# main_16_writer.net
KiCad netlist of a schematic drawn in EAGLE
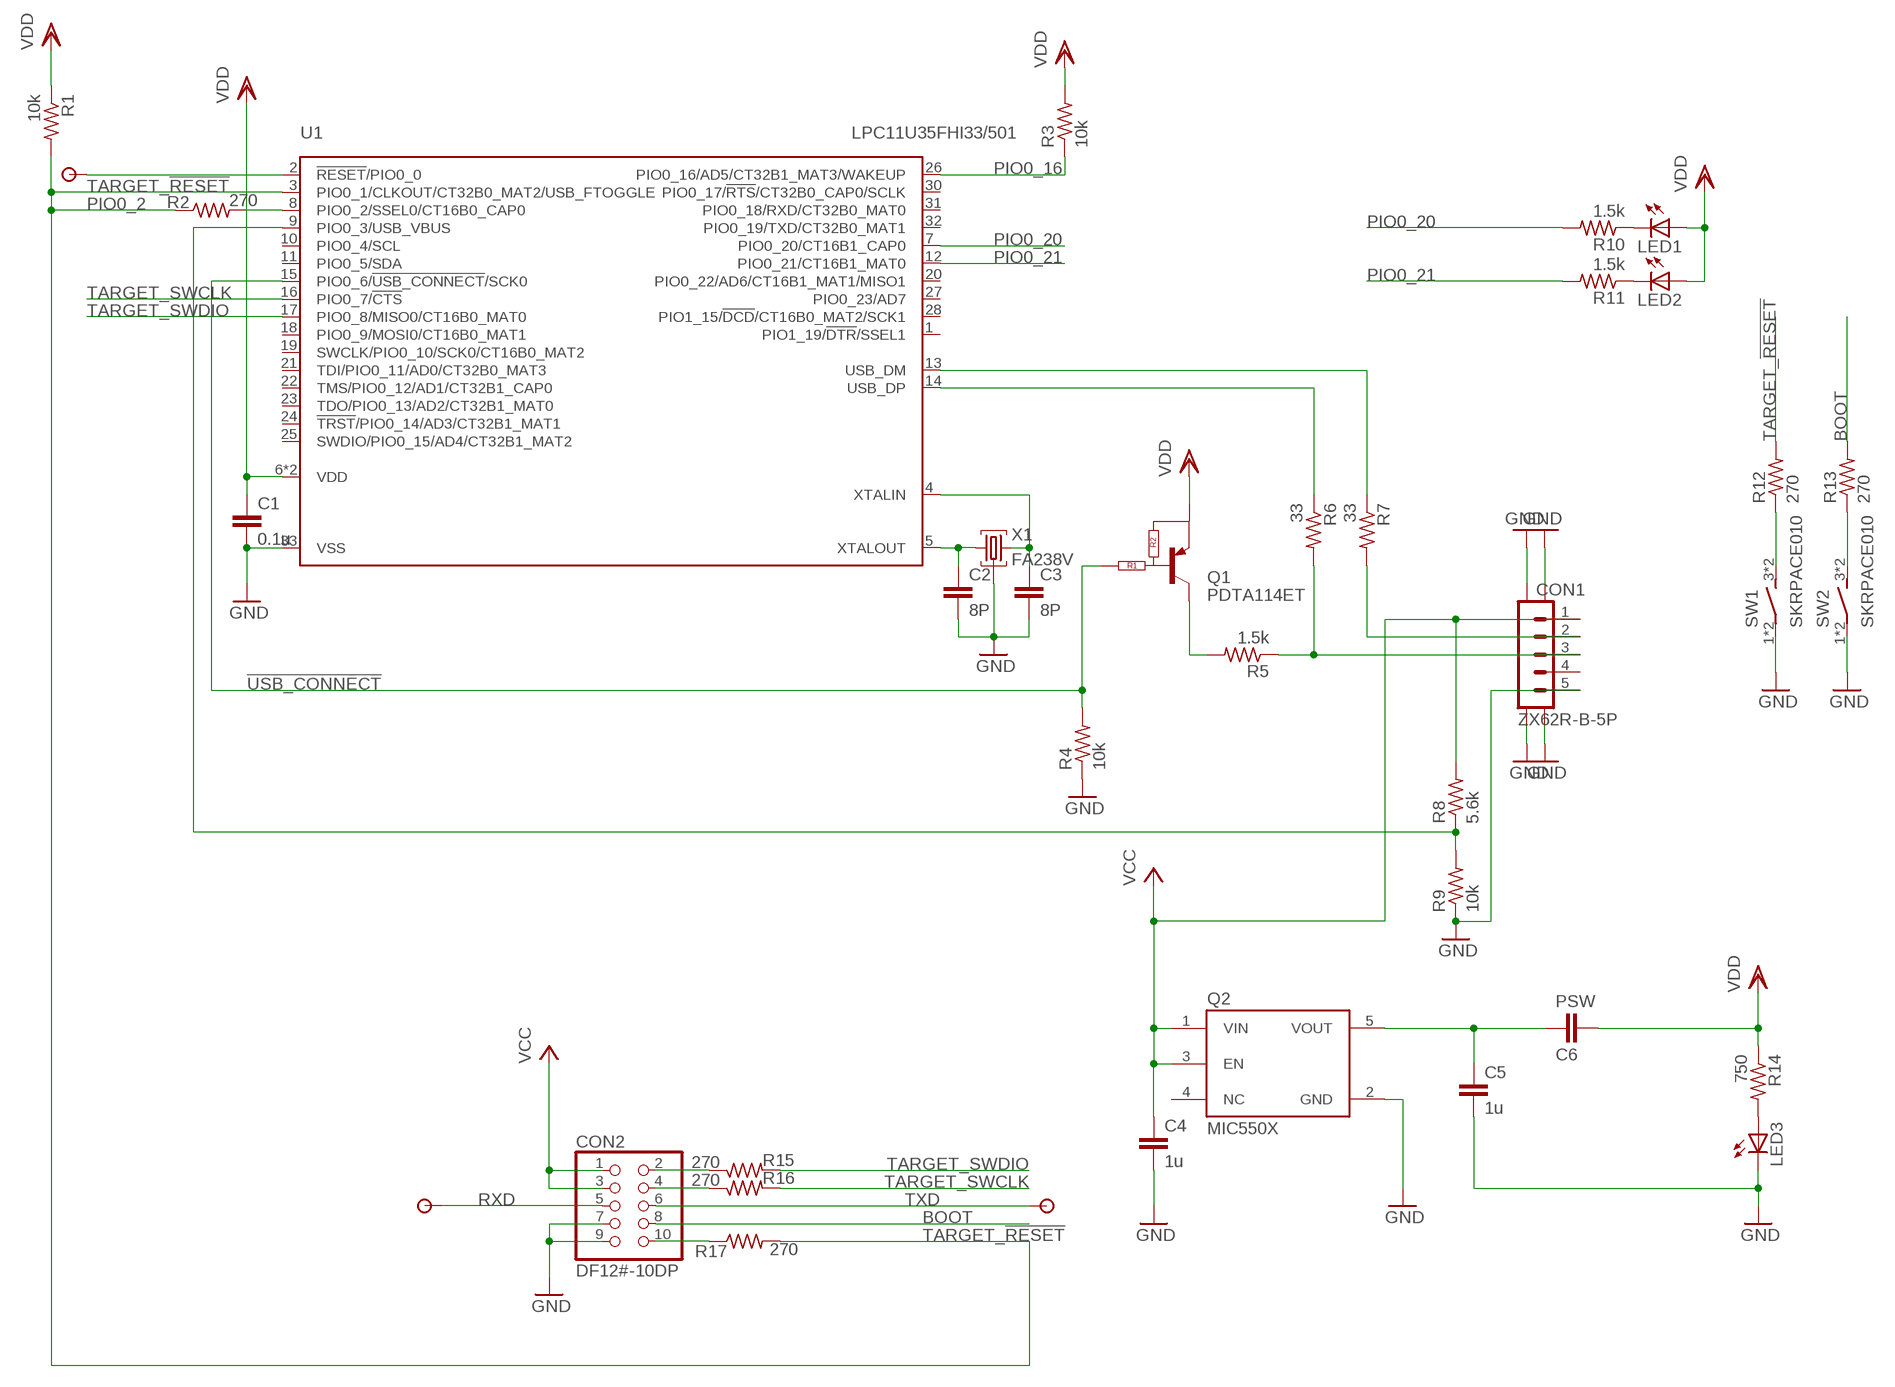
[diagram p0: schematic, sheet 1]

(export (version "E")
  (design (tool "Eeschema 10.0.6"))
  (components
    (comp (ref "C1")
      (value "0.1u")
      (footprint "eagle-import:C0402")
      (libsource (lib "eagle-import") (part "C-EUC0402"))
    )
    (comp (ref "C2")
      (value "8P")
      (footprint "eagle-import:C0402")
      (libsource (lib "eagle-import") (part "C-EUC0402"))
    )
    (comp (ref "C3")
      (value "8P")
      (footprint "eagle-import:C0402")
      (libsource (lib "eagle-import") (part "C-EUC0402"))
    )
    (comp (ref "C4")
      (value "1u")
      (footprint "eagle-import:C0402")
      (libsource (lib "eagle-import") (part "C-EUC0402"))
    )
    (comp (ref "C5")
      (value "1u")
      (footprint "eagle-import:C0402")
      (libsource (lib "eagle-import") (part "C-EUC0402"))
    )
    (comp (ref "C6")
      (value "PSW")
      (footprint "eagle-import:C3225")
      (libsource (lib "eagle-import") (part "C-EUC3225"))
    )
    (comp (ref "CON1")
      (value "ZX62R-B-5P")
      (footprint "eagle-import:MICRO-B")
      (libsource (lib "eagle-import") (part "ZX62R-B-5P"))
    )
    (comp (ref "CON2")
      (value "DF12#-10DP")
      (footprint "eagle-import:DF12D-10DP")
      (libsource (lib "eagle-import") (part "DF12#-10DP"))
    )
    (comp (ref "LED1")
      (value "LEDSML0603")
      (footprint "eagle-import:SML0603")
      (libsource (lib "eagle-import") (part "LEDSML0603"))
    )
    (comp (ref "LED2")
      (value "LEDSML0603")
      (footprint "eagle-import:SML0603")
      (libsource (lib "eagle-import") (part "LEDSML0603"))
    )
    (comp (ref "LED3")
      (value "LEDSML0603")
      (footprint "eagle-import:SML0603")
      (libsource (lib "eagle-import") (part "LEDSML0603"))
    )
    (comp (ref "Q1")
      (value "PDTA114ET")
      (footprint "eagle-import:SOT23")
      (libsource (lib "eagle-import") (part "PDTA114TE"))
    )
    (comp (ref "Q2")
      (value "MIC550X")
      (footprint "eagle-import:SOT23_5PIN")
      (libsource (lib "eagle-import") (part "MIC550X"))
    )
    (comp (ref "R1")
      (value "10k")
      (footprint "eagle-import:R0402")
      (libsource (lib "eagle-import") (part "R-US_R0402"))
    )
    (comp (ref "R2")
      (value "270")
      (footprint "eagle-import:R0402")
      (libsource (lib "eagle-import") (part "R-US_R0402"))
    )
    (comp (ref "R3")
      (value "10k")
      (footprint "eagle-import:R0402")
      (libsource (lib "eagle-import") (part "R-US_R0402"))
    )
    (comp (ref "R4")
      (value "10k")
      (footprint "eagle-import:R0402")
      (libsource (lib "eagle-import") (part "R-US_R0402"))
    )
    (comp (ref "R5")
      (value "1.5k")
      (footprint "eagle-import:R0402")
      (libsource (lib "eagle-import") (part "R-US_R0402"))
    )
    (comp (ref "R6")
      (value "33")
      (footprint "eagle-import:R0402")
      (libsource (lib "eagle-import") (part "R-US_R0402"))
    )
    (comp (ref "R7")
      (value "33")
      (footprint "eagle-import:R0402")
      (libsource (lib "eagle-import") (part "R-US_R0402"))
    )
    (comp (ref "R8")
      (value "5.6k")
      (footprint "eagle-import:R0402")
      (libsource (lib "eagle-import") (part "R-US_R0402"))
    )
    (comp (ref "R9")
      (value "10k")
      (footprint "eagle-import:R0402")
      (libsource (lib "eagle-import") (part "R-US_R0402"))
    )
    (comp (ref "R10")
      (value "1.5k")
      (footprint "eagle-import:R0402")
      (libsource (lib "eagle-import") (part "R-US_R0402"))
    )
    (comp (ref "R11")
      (value "1.5k")
      (footprint "eagle-import:R0402")
      (libsource (lib "eagle-import") (part "R-US_R0402"))
    )
    (comp (ref "R12")
      (value "270")
      (footprint "eagle-import:R0402")
      (libsource (lib "eagle-import") (part "R-US_R0402"))
    )
    (comp (ref "R13")
      (value "270")
      (footprint "eagle-import:R0402")
      (libsource (lib "eagle-import") (part "R-US_R0402"))
    )
    (comp (ref "R14")
      (value "750")
      (footprint "eagle-import:R0402")
      (libsource (lib "eagle-import") (part "R-US_R0402"))
    )
    (comp (ref "R15")
      (value "270")
      (footprint "eagle-import:R0402")
      (libsource (lib "eagle-import") (part "R-US_R0402"))
    )
    (comp (ref "R16")
      (value "270")
      (footprint "eagle-import:R0402")
      (libsource (lib "eagle-import") (part "R-US_R0402"))
    )
    (comp (ref "R17")
      (value "270")
      (footprint "eagle-import:R0402")
      (libsource (lib "eagle-import") (part "R-US_R0402"))
    )
    (comp (ref "SW1")
      (value "SKRPACE010")
      (footprint "eagle-import:SKRPACE010")
      (libsource (lib "eagle-import") (part "SKRPACE010"))
    )
    (comp (ref "SW2")
      (value "SKRPACE010")
      (footprint "eagle-import:SKRPACE010")
      (libsource (lib "eagle-import") (part "SKRPACE010"))
    )
    (comp (ref "U$1")
      (value "TESTPAD")
      (footprint "eagle-import:TESTPAD")
      (libsource (lib "eagle-import") (part "TESTPAD"))
    )
    (comp (ref "U$2")
      (value "TESTPAD")
      (footprint "eagle-import:TESTPAD")
      (libsource (lib "eagle-import") (part "TESTPAD"))
    )
    (comp (ref "U$3")
      (value "TESTPAD")
      (footprint "eagle-import:TESTPAD")
      (libsource (lib "eagle-import") (part "TESTPAD"))
    )
    (comp (ref "U1")
      (value "LPC11U35FHI33/501")
      (footprint "eagle-import:SOT617-3")
      (libsource (lib "eagle-import") (part "LPC11U35FHI33/501"))
    )
    (comp (ref "X1")
      (value "FA238V")
      (footprint "eagle-import:V66RA")
      (libsource (lib "eagle-import") (part "FA238V"))
    )
  )
  (nets
    (net (code "1") (name "/BOOT") (class "Default")
      (node (ref "CON2") (pin "8") (pinfunction "8_8") (pintype "passive"))
      (node (ref "R13") (pin "2") (pinfunction "2_2") (pintype "passive"))
    )
    (net (code "2") (name "/PIO0_2") (class "Default")
      (node (ref "R2") (pin "2") (pinfunction "2_2") (pintype "passive"))
      (node (ref "U1") (pin "8") (pinfunction "PIO0_2/SSEL0/CT16B0_CAP0_8") (pintype "bidirectional"))
    )
    (net (code "3") (name "/PIO0_16") (class "Default")
      (node (ref "R3") (pin "1") (pinfunction "1_1") (pintype "passive"))
      (node (ref "U1") (pin "26") (pinfunction "PIO0_16/AD5/CT32B1_MAT3/WAKEUP_26") (pintype "bidirectional"))
    )
    (net (code "4") (name "/PIO0_20") (class "Default")
      (node (ref "R10") (pin "2") (pinfunction "2_2") (pintype "passive"))
      (node (ref "U1") (pin "7") (pinfunction "PIO0_20/CT16B1_CAP0_7") (pintype "bidirectional"))
    )
    (net (code "5") (name "/PIO0_21") (class "Default")
      (node (ref "R11") (pin "2") (pinfunction "2_2") (pintype "passive"))
      (node (ref "U1") (pin "12") (pinfunction "PIO0_21/CT16B1_MAT0_12") (pintype "bidirectional"))
    )
    (net (code "6") (name "/RXD") (class "Default")
      (node (ref "CON2") (pin "5") (pinfunction "5_5") (pintype "passive"))
      (node (ref "U$2") (pin "P$1") (pinfunction "P$1_P$1") (pintype "passive"))
    )
    (net (code "7") (name "/TARGET_SWCLK") (class "Default")
      (node (ref "R16") (pin "2") (pinfunction "2_2") (pintype "passive"))
      (node (ref "U1") (pin "16") (pinfunction "PIO0_7/~{CTS}_16") (pintype "bidirectional"))
    )
    (net (code "8") (name "/TARGET_SWDIO") (class "Default")
      (node (ref "R15") (pin "2") (pinfunction "2_2") (pintype "passive"))
      (node (ref "U1") (pin "17") (pinfunction "PIO0_8/MISO0/CT16B0_MAT0_17") (pintype "bidirectional"))
    )
    (net (code "9") (name "/TARGET_~{RESET}") (class "Default")
      (node (ref "R1") (pin "2") (pinfunction "2_2") (pintype "passive"))
      (node (ref "R12") (pin "2") (pinfunction "2_2") (pintype "passive"))
      (node (ref "R17") (pin "2") (pinfunction "2_2") (pintype "passive"))
      (node (ref "R2") (pin "1") (pinfunction "1_1") (pintype "passive"))
      (node (ref "U1") (pin "3") (pinfunction "PIO0_1/CLKOUT/CT32B0_MAT2/USB_FTOGGLE_3") (pintype "bidirectional"))
    )
    (net (code "10") (name "/TXD") (class "Default")
      (node (ref "CON2") (pin "6") (pinfunction "6_6") (pintype "passive"))
      (node (ref "U$1") (pin "P$1") (pinfunction "P$1_P$1") (pintype "passive"))
    )
    (net (code "11") (name "/~{USB_CONNECT}") (class "Default")
      (node (ref "Q1") (pin "1") (pinfunction "INPUT_1") (pintype "passive"))
      (node (ref "R4") (pin "2") (pinfunction "2_2") (pintype "passive"))
      (node (ref "U1") (pin "15") (pinfunction "PIO0_6/~{USB_CONNECT}/SCK0_15") (pintype "bidirectional"))
    )
    (net (code "12") (name "GND") (class "Default")
      (node (ref "C1") (pin "2") (pinfunction "2_2") (pintype "passive"))
      (node (ref "C2") (pin "2") (pinfunction "2_2") (pintype "passive"))
      (node (ref "C3") (pin "2") (pinfunction "2_2") (pintype "passive"))
      (node (ref "C4") (pin "2") (pinfunction "2_2") (pintype "passive"))
      (node (ref "C5") (pin "2") (pinfunction "2_2") (pintype "passive"))
      (node (ref "CON1") (pin "5") (pinfunction "1.VBUS_5") (pintype "passive"))
      (node (ref "CON1") (pin "CASE@1") (pinfunction "1_CASE@1") (pintype "bidirectional"))
      (node (ref "CON1") (pin "CASE@2") (pinfunction "2_CASE@2") (pintype "bidirectional"))
      (node (ref "CON1") (pin "CASE@3") (pinfunction "3_CASE@3") (pintype "bidirectional"))
      (node (ref "CON1") (pin "CASE@4") (pinfunction "4_CASE@4") (pintype "bidirectional"))
      (node (ref "CON2") (pin "7") (pinfunction "7_7") (pintype "passive"))
      (node (ref "CON2") (pin "9") (pinfunction "9_9") (pintype "passive"))
      (node (ref "LED3") (pin "C") (pinfunction "C_C") (pintype "passive"))
      (node (ref "Q2") (pin "2") (pinfunction "GND_2") (pintype "power_in"))
      (node (ref "R4") (pin "1") (pinfunction "1_1") (pintype "passive"))
      (node (ref "R9") (pin "1") (pinfunction "1_1") (pintype "passive"))
      (node (ref "SW1") (pin "1") (pinfunction "P_1") (pintype "passive"))
      (node (ref "SW1") (pin "2") (pinfunction "P_2") (pintype "passive"))
      (node (ref "SW2") (pin "1") (pinfunction "P_1") (pintype "passive"))
      (node (ref "SW2") (pin "2") (pinfunction "P_2") (pintype "passive"))
      (node (ref "U1") (pin "33") (pinfunction "VSS_33") (pintype "power_in"))
      (node (ref "X1") (pin "P2GND") (pinfunction "GND_P2GND") (pintype "bidirectional"))
      (node (ref "X1") (pin "P4GND") (pinfunction "GND_P4GND") (pintype "bidirectional"))
    )
    (net (code "13") (name "Net-(CON1-3.D+)") (class "Default")
      (node (ref "CON1") (pin "3") (pinfunction "3.D+_3") (pintype "passive"))
      (node (ref "R5") (pin "1") (pinfunction "1_1") (pintype "passive"))
      (node (ref "R6") (pin "2") (pinfunction "2_2") (pintype "passive"))
    )
    (net (code "14") (name "Net-(CON1-4.ID)") (class "Default")
      (node (ref "CON1") (pin "2") (pinfunction "4.ID_2") (pintype "passive"))
      (node (ref "R7") (pin "2") (pinfunction "2_2") (pintype "passive"))
    )
    (net (code "15") (name "Net-(CON2-Pad2)") (class "Default")
      (node (ref "CON2") (pin "2") (pinfunction "2_2") (pintype "passive"))
      (node (ref "R15") (pin "1") (pinfunction "1_1") (pintype "passive"))
    )
    (net (code "16") (name "Net-(CON2-Pad4)") (class "Default")
      (node (ref "CON2") (pin "4") (pinfunction "4_4") (pintype "passive"))
      (node (ref "R16") (pin "1") (pinfunction "1_1") (pintype "passive"))
    )
    (net (code "17") (name "Net-(CON2-Pad10)") (class "Default")
      (node (ref "CON2") (pin "10") (pinfunction "10_10") (pintype "passive"))
      (node (ref "R17") (pin "1") (pinfunction "1_1") (pintype "passive"))
    )
    (net (code "18") (name "Net-(LED1-PadC)") (class "Default")
      (node (ref "LED1") (pin "C") (pinfunction "C_C") (pintype "passive"))
      (node (ref "R10") (pin "1") (pinfunction "1_1") (pintype "passive"))
    )
    (net (code "19") (name "Net-(LED2-PadC)") (class "Default")
      (node (ref "LED2") (pin "C") (pinfunction "C_C") (pintype "passive"))
      (node (ref "R11") (pin "1") (pinfunction "1_1") (pintype "passive"))
    )
    (net (code "20") (name "Net-(LED3-PadA)") (class "Default")
      (node (ref "LED3") (pin "A") (pinfunction "A_A") (pintype "passive"))
      (node (ref "R14") (pin "2") (pinfunction "2_2") (pintype "passive"))
    )
    (net (code "21") (name "Net-(Q1-C)") (class "Default")
      (node (ref "Q1") (pin "3") (pinfunction "C_3") (pintype "passive"))
      (node (ref "R5") (pin "2") (pinfunction "2_2") (pintype "passive"))
    )
    (net (code "22") (name "Net-(Q2-VOUT)") (class "Default")
      (node (ref "C5") (pin "1") (pinfunction "1_1") (pintype "passive"))
      (node (ref "C6") (pin "2") (pinfunction "2_2") (pintype "passive"))
      (node (ref "Q2") (pin "5") (pinfunction "VOUT_5") (pintype "output"))
    )
    (net (code "23") (name "Net-(R12-Pad1)") (class "Default")
      (node (ref "R12") (pin "1") (pinfunction "1_1") (pintype "passive"))
      (node (ref "SW1") (pin "3") (pinfunction "S_3") (pintype "passive"))
      (node (ref "SW1") (pin "4") (pinfunction "S_4") (pintype "passive"))
    )
    (net (code "24") (name "Net-(R13-Pad1)") (class "Default")
      (node (ref "R13") (pin "1") (pinfunction "1_1") (pintype "passive"))
      (node (ref "SW2") (pin "3") (pinfunction "S_3") (pintype "passive"))
      (node (ref "SW2") (pin "4") (pinfunction "S_4") (pintype "passive"))
    )
    (net (code "25") (name "Net-(U1-PIO0_3{slash}USB_VBUS)") (class "Default")
      (node (ref "R8") (pin "1") (pinfunction "1_1") (pintype "passive"))
      (node (ref "R9") (pin "2") (pinfunction "2_2") (pintype "passive"))
      (node (ref "U1") (pin "9") (pinfunction "PIO0_3/USB_VBUS_9") (pintype "bidirectional"))
    )
    (net (code "26") (name "Net-(U1-USB_DM)") (class "Default")
      (node (ref "R7") (pin "1") (pinfunction "1_1") (pintype "passive"))
      (node (ref "U1") (pin "13") (pinfunction "USB_DM_13") (pintype "bidirectional"))
    )
    (net (code "27") (name "Net-(U1-USB_DP)") (class "Default")
      (node (ref "R6") (pin "1") (pinfunction "1_1") (pintype "passive"))
      (node (ref "U1") (pin "14") (pinfunction "USB_DP_14") (pintype "bidirectional"))
    )
    (net (code "28") (name "Net-(U1-XTALIN)") (class "Default")
      (node (ref "C3") (pin "1") (pinfunction "1_1") (pintype "passive"))
      (node (ref "U1") (pin "4") (pinfunction "XTALIN_4") (pintype "input"))
      (node (ref "X1") (pin "P3X2") (pinfunction "X2_P3X2") (pintype "output"))
    )
    (net (code "29") (name "Net-(U1-XTALOUT)") (class "Default")
      (node (ref "C2") (pin "1") (pinfunction "1_1") (pintype "passive"))
      (node (ref "U1") (pin "5") (pinfunction "XTALOUT_5") (pintype "output"))
      (node (ref "X1") (pin "P1X1") (pinfunction "X1_P1X1") (pintype "output"))
    )
    (net (code "30") (name "Net-(U1-~{RESET}{slash}PIO0_0)") (class "Default")
      (node (ref "U$3") (pin "P$1") (pinfunction "P$1_P$1") (pintype "passive"))
      (node (ref "U1") (pin "2") (pinfunction "~{RESET}/PIO0_0_2") (pintype "bidirectional"))
    )
    (net (code "31") (name "VCC") (class "Default")
      (node (ref "C4") (pin "1") (pinfunction "1_1") (pintype "passive"))
      (node (ref "CON1") (pin "1") (pinfunction "5.GND_1") (pintype "passive"))
      (node (ref "CON2") (pin "1") (pinfunction "1_1") (pintype "passive"))
      (node (ref "CON2") (pin "3") (pinfunction "3_3") (pintype "passive"))
      (node (ref "Q2") (pin "1") (pinfunction "VIN_1") (pintype "input"))
      (node (ref "Q2") (pin "3") (pinfunction "EN_3") (pintype "input"))
      (node (ref "R8") (pin "2") (pinfunction "2_2") (pintype "passive"))
    )
    (net (code "32") (name "VDD") (class "Default")
      (node (ref "C1") (pin "1") (pinfunction "1_1") (pintype "passive"))
      (node (ref "C6") (pin "1") (pinfunction "1_1") (pintype "passive"))
      (node (ref "LED1") (pin "A") (pinfunction "A_A") (pintype "passive"))
      (node (ref "LED2") (pin "A") (pinfunction "A_A") (pintype "passive"))
      (node (ref "Q1") (pin "2") (pinfunction "E_2") (pintype "passive"))
      (node (ref "R1") (pin "1") (pinfunction "1_1") (pintype "passive"))
      (node (ref "R14") (pin "1") (pinfunction "1_1") (pintype "passive"))
      (node (ref "R3") (pin "2") (pinfunction "2_2") (pintype "passive"))
      (node (ref "U1") (pin "29") (pinfunction "VDD_29") (pintype "power_in"))
      (node (ref "U1") (pin "6") (pinfunction "VDD_6") (pintype "power_in"))
    )
    (net (code "33") (name "unconnected-(CON1-2.D--Pad4)") (class "Default")
      (node (ref "CON1") (pin "4") (pinfunction "2.D-_4") (pintype "passive"))
    )
    (net (code "34") (name "unconnected-(Q2-NC-Pad4)") (class "Default")
      (node (ref "Q2") (pin "4") (pinfunction "NC_4") (pintype "no_connect"))
    )
    (net (code "35") (name "unconnected-(U1-PIO0_4{slash}SCL-Pad10)") (class "Default")
      (node (ref "U1") (pin "10") (pinfunction "PIO0_4/SCL_10") (pintype "bidirectional"))
    )
    (net (code "36") (name "unconnected-(U1-PIO0_5{slash}SDA-Pad11)") (class "Default")
      (node (ref "U1") (pin "11") (pinfunction "PIO0_5/SDA_11") (pintype "bidirectional"))
    )
    (net (code "37") (name "unconnected-(U1-PIO0_9{slash}MOSI0{slash}CT16B0_MAT1-Pad18)") (class "Default")
      (node (ref "U1") (pin "18") (pinfunction "PIO0_9/MOSI0/CT16B0_MAT1_18") (pintype "bidirectional"))
    )
    (net (code "38") (name "unconnected-(U1-PIO0_17{slash}~{RTS}{slash}CT32B0_CAP0{slash}SCLK-Pad30)") (class "Default")
      (node (ref "U1") (pin "30") (pinfunction "PIO0_17/~{RTS}/CT32B0_CAP0/SCLK_30") (pintype "bidirectional"))
    )
    (net (code "39") (name "unconnected-(U1-PIO0_18{slash}RXD{slash}CT32B0_MAT0-Pad31)") (class "Default")
      (node (ref "U1") (pin "31") (pinfunction "PIO0_18/RXD/CT32B0_MAT0_31") (pintype "bidirectional"))
    )
    (net (code "40") (name "unconnected-(U1-PIO0_19{slash}TXD{slash}CT32B0_MAT1-Pad32)") (class "Default")
      (node (ref "U1") (pin "32") (pinfunction "PIO0_19/TXD/CT32B0_MAT1_32") (pintype "bidirectional"))
    )
    (net (code "41") (name "unconnected-(U1-PIO0_22{slash}AD6{slash}CT16B1_MAT1{slash}MISO1-Pad20)") (class "Default")
      (node (ref "U1") (pin "20") (pinfunction "PIO0_22/AD6/CT16B1_MAT1/MISO1_20") (pintype "bidirectional"))
    )
    (net (code "42") (name "unconnected-(U1-PIO0_23{slash}AD7-Pad27)") (class "Default")
      (node (ref "U1") (pin "27") (pinfunction "PIO0_23/AD7_27") (pintype "bidirectional"))
    )
    (net (code "43") (name "unconnected-(U1-PIO1_15{slash}~{DCD}{slash}CT16B0_MAT2{slash}SCK1-Pad28)") (class "Default")
      (node (ref "U1") (pin "28") (pinfunction "PIO1_15/~{DCD}/CT16B0_MAT2/SCK1_28") (pintype "bidirectional"))
    )
    (net (code "44") (name "unconnected-(U1-PIO1_19{slash}~{DTR}{slash}SSEL1-Pad1)") (class "Default")
      (node (ref "U1") (pin "1") (pinfunction "PIO1_19/~{DTR}/SSEL1_1") (pintype "bidirectional"))
    )
    (net (code "45") (name "unconnected-(U1-SWCLK{slash}PIO0_10{slash}SCK0{slash}CT16B0_MAT2-Pad19)") (class "Default")
      (node (ref "U1") (pin "19") (pinfunction "SWCLK/PIO0_10/SCK0/CT16B0_MAT2_19") (pintype "bidirectional"))
    )
    (net (code "46") (name "unconnected-(U1-SWDIO{slash}PIO0_15{slash}AD4{slash}CT32B1_MAT2-Pad25)") (class "Default")
      (node (ref "U1") (pin "25") (pinfunction "SWDIO/PIO0_15/AD4/CT32B1_MAT2_25") (pintype "bidirectional"))
    )
    (net (code "47") (name "unconnected-(U1-TDI{slash}PIO0_11{slash}AD0{slash}CT32B0_MAT3-Pad21)") (class "Default")
      (node (ref "U1") (pin "21") (pinfunction "TDI/PIO0_11/AD0/CT32B0_MAT3_21") (pintype "bidirectional"))
    )
    (net (code "48") (name "unconnected-(U1-TDO{slash}PIO0_13{slash}AD2{slash}CT32B1_MAT0-Pad23)") (class "Default")
      (node (ref "U1") (pin "23") (pinfunction "TDO/PIO0_13/AD2/CT32B1_MAT0_23") (pintype "bidirectional"))
    )
    (net (code "49") (name "unconnected-(U1-TMS{slash}PIO0_12{slash}AD1{slash}CT32B1_CAP0-Pad22)") (class "Default")
      (node (ref "U1") (pin "22") (pinfunction "TMS/PIO0_12/AD1/CT32B1_CAP0_22") (pintype "bidirectional"))
    )
    (net (code "50") (name "unconnected-(U1-~{TRST}{slash}PIO0_14{slash}AD3{slash}CT32B1_MAT1-Pad24)") (class "Default")
      (node (ref "U1") (pin "24") (pinfunction "~{TRST}/PIO0_14/AD3/CT32B1_MAT1_24") (pintype "bidirectional"))
    )
  )
)
